# Encoder.net
KiCad netlist of a schematic drawn in Altium Designer
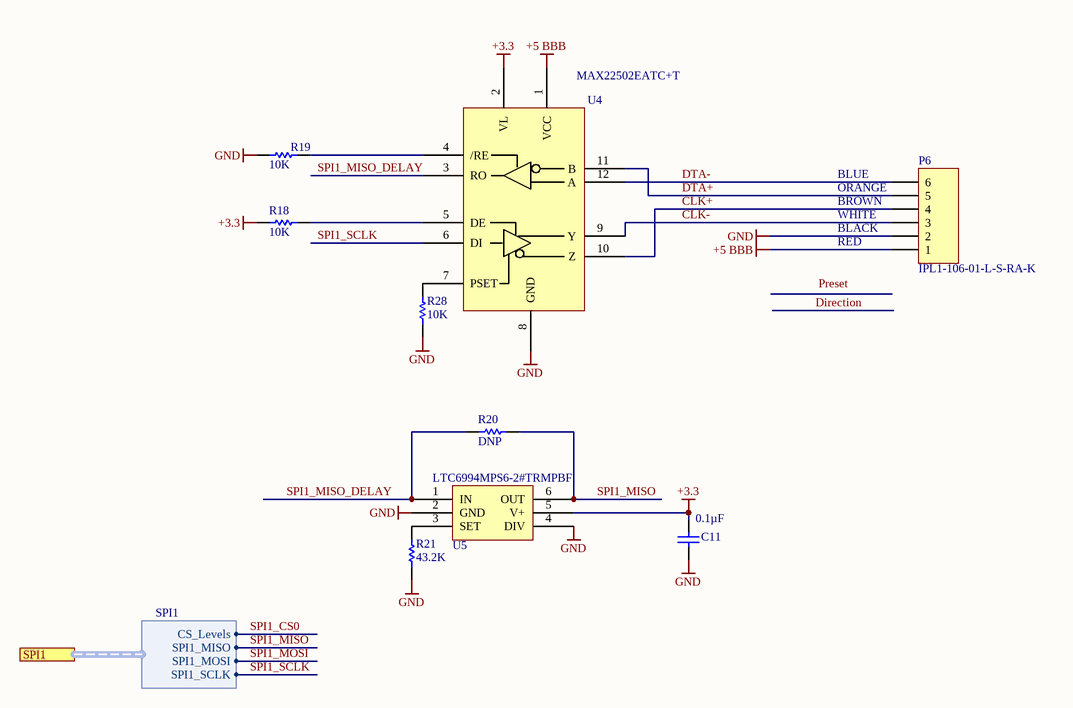
[diagram p0: Encoder.SchDoc]

(export (version "E")
  (design (tool "Eeschema 10.0.6"))
  (components
    (comp (ref "C11")
      (value "CAP CER 0.1UF 25V X7R 0805")
      (footprint "CAPC0805(2012)145_N")
      (fields
        (field (name "MANUFACTURER") "Murata Electronics North America")
        (field (name "MANUFACTURER PART NUMBER") "GRM21BR71E104KA01L")
        (field (name "CAPACITANCE") "0.1µF")
        (field (name "TOLERANCE") "±10%")
      )
      (libsource (lib "Altium Content Vault") (part "CMP-1036-04795-1"))
    )
    (comp (ref "P6")
      (value "IPL1-106-01-L-S-RA-K")
      (footprint "IPL1-106-01-L-S-RA-K")
      (description "Header, 6-Pin")
      (fields (field (name "MANUFACTURER") "Samtec Inc."))
      (libsource (lib "Miscellaneous Connectors") (part "Header 6"))
    )
    (comp (ref "R18")
      (value "10K")
      (footprint "RESC0805(2012)_L")
      (description "RES SMD 10K OHM 1% 1/8W 0805")
      (fields
        (field (name "MANUFACTURER") "Vishay Dale")
        (field (name "MANUFACTURER PART NUMBER") "CRCW080510K0FKEA")
      )
      (libsource (lib "Altium Content Vault") (part "CMP-1013-00215-1"))
    )
    (comp (ref "R19")
      (value "10K")
      (footprint "RESC0805(2012)_L")
      (description "RES SMD 10K OHM 1% 1/8W 0805")
      (fields
        (field (name "MANUFACTURER") "Vishay Dale")
        (field (name "MANUFACTURER PART NUMBER") "CRCW080510K0FKEA")
      )
      (libsource (lib "Altium Content Vault") (part "CMP-1013-00215-1"))
    )
    (comp (ref "R20")
      (value "DNP")
      (footprint "RESC0805(2012)_L")
      (description "RES SMD 0 OHM 5% 1/8W 0805")
      (libsource (lib "Altium Content Vault") (part "CMP-1013-00215-1"))
    )
    (comp (ref "R21")
      (value "43.2K")
      (footprint "RESC0805(2012)_L")
      (description "RES SMD 43.2K OHM 1% 1/8W 0805")
      (fields
        (field (name "MANUFACTURER") "Vishay Dale")
        (field (name "MANUFACTURER PART NUMBER") "CRCW080543K2FKEA")
      )
      (libsource (lib "Altium Content Vault") (part "CMP-1013-00215-1"))
    )
    (comp (ref "R28")
      (value "10K")
      (footprint "RESC0805(2012)_L")
      (description "RES SMD 10K OHM 1% 1/8W 0805")
      (fields
        (field (name "MANUFACTURER") "Vishay Dale")
        (field (name "MANUFACTURER PART NUMBER") "CRCW080510K0FKEA")
      )
      (libsource (lib "Altium Content Vault") (part "CMP-1013-00215-1"))
    )
    (comp (ref "U4")
      (value "MAX22502EATC+T")
      (footprint "MAX22502EATC+T")
      (libsource (lib "ZLS_Schematic_lib") (part "MAX22502EATC+T"))
    )
    (comp (ref "U5")
      (value "LTC6994MPS6-2#TRMPBF")
      (footprint "LTC6994MPS6-2#TRMPBF")
      (fields
        (field (name "MANUFACTURER") "Linear Technology/Analog Devices")
        (field (name "MANUFACTURER PART NUMBER") "LTC6994CS6-2#TRMPBF")
        (field (name "BASE PART NUMBER") "LTC6994")
      )
      (libsource (lib "ZLS_Schematic_lib") (part "LTC6994MPS6-2#TRMPBF"))
    )
  )
  (nets
    (net (code "2") (name "+3.3") (class "Default")
      (node (ref "C11") (pin "1") (pinfunction "1_1") (pintype "passive"))
      (node (ref "R18") (pin "2") (pinfunction "2_2") (pintype "passive"))
      (node (ref "U4") (pin "2") (pinfunction "VL_2") (pintype "passive"))
      (node (ref "U5") (pin "5") (pinfunction "V+_5") (pintype "passive"))
    )
    (net (code "3") (name "+5 BBB") (class "Default")
      (node (ref "P6") (pin "1") (pinfunction "1_1") (pintype "passive"))
      (node (ref "U4") (pin "1") (pinfunction "VCC_1") (pintype "passive"))
    )
    (net (code "4") (name "/CLK+") (class "Default")
      (node (ref "P6") (pin "4") (pinfunction "4_4") (pintype "passive"))
      (node (ref "U4") (pin "10") (pinfunction "Z_10") (pintype "passive"))
    )
    (net (code "5") (name "/CLK-") (class "Default")
      (node (ref "P6") (pin "3") (pinfunction "3_3") (pintype "passive"))
      (node (ref "U4") (pin "9") (pinfunction "Y_9") (pintype "passive"))
    )
    (net (code "6") (name "/DTA+") (class "Default")
      (node (ref "P6") (pin "5") (pinfunction "5_5") (pintype "passive"))
      (node (ref "U4") (pin "11") (pinfunction "B_11") (pintype "passive"))
    )
    (net (code "7") (name "/DTA-") (class "Default")
      (node (ref "P6") (pin "6") (pinfunction "6_6") (pintype "passive"))
      (node (ref "U4") (pin "12") (pinfunction "A_12") (pintype "passive"))
    )
    (net (code "11") (name "/SPI1_MISO") (class "Default")
      (node (ref "R20") (pin "2") (pinfunction "2_2") (pintype "passive"))
      (node (ref "U5") (pin "6") (pinfunction "OUT_6") (pintype "passive"))
    )
    (net (code "12") (name "/SPI1_MISO_DELAY") (class "Default")
      (node (ref "R20") (pin "1") (pinfunction "1_1") (pintype "passive"))
      (node (ref "U4") (pin "3") (pinfunction "RO_3") (pintype "passive"))
      (node (ref "U5") (pin "1") (pinfunction "IN_1") (pintype "passive"))
    )
    (net (code "14") (name "/SPI1_SCLK") (class "Default")
      (node (ref "U4") (pin "6") (pinfunction "DI_6") (pintype "passive"))
    )
    (net (code "16") (name "GND") (class "Default")
      (node (ref "C11") (pin "2") (pinfunction "2_2") (pintype "passive"))
      (node (ref "P6") (pin "2") (pinfunction "2_2") (pintype "passive"))
      (node (ref "R19") (pin "2") (pinfunction "2_2") (pintype "passive"))
      (node (ref "R21") (pin "2") (pinfunction "2_2") (pintype "passive"))
      (node (ref "R28") (pin "2") (pinfunction "2_2") (pintype "passive"))
      (node (ref "U4") (pin "8") (pinfunction "GND_8") (pintype "passive"))
      (node (ref "U5") (pin "2") (pinfunction "GND_2") (pintype "passive"))
      (node (ref "U5") (pin "4") (pinfunction "DIV_4") (pintype "passive"))
    )
    (net (code "17") (name "Net-(U4-DE)") (class "Default")
      (node (ref "R18") (pin "1") (pinfunction "1_1") (pintype "passive"))
      (node (ref "U4") (pin "5") (pinfunction "DE_5") (pintype "passive"))
    )
    (net (code "18") (name "Net-(U4-PSET)") (class "Default")
      (node (ref "R28") (pin "1") (pinfunction "1_1") (pintype "passive"))
      (node (ref "U4") (pin "7") (pinfunction "PSET_7") (pintype "passive"))
    )
    (net (code "19") (name "Net-(U4-{slash}RE)") (class "Default")
      (node (ref "R19") (pin "1") (pinfunction "1_1") (pintype "passive"))
      (node (ref "U4") (pin "4") (pinfunction "/RE_4") (pintype "passive"))
    )
    (net (code "20") (name "Net-(U5-SET)") (class "Default")
      (node (ref "R21") (pin "1") (pinfunction "1_1") (pintype "passive"))
      (node (ref "U5") (pin "3") (pinfunction "SET_3") (pintype "passive"))
    )
  )
)
